# BrauV2_Power.net
KiCad netlist of a schematic drawn in Altium Designer
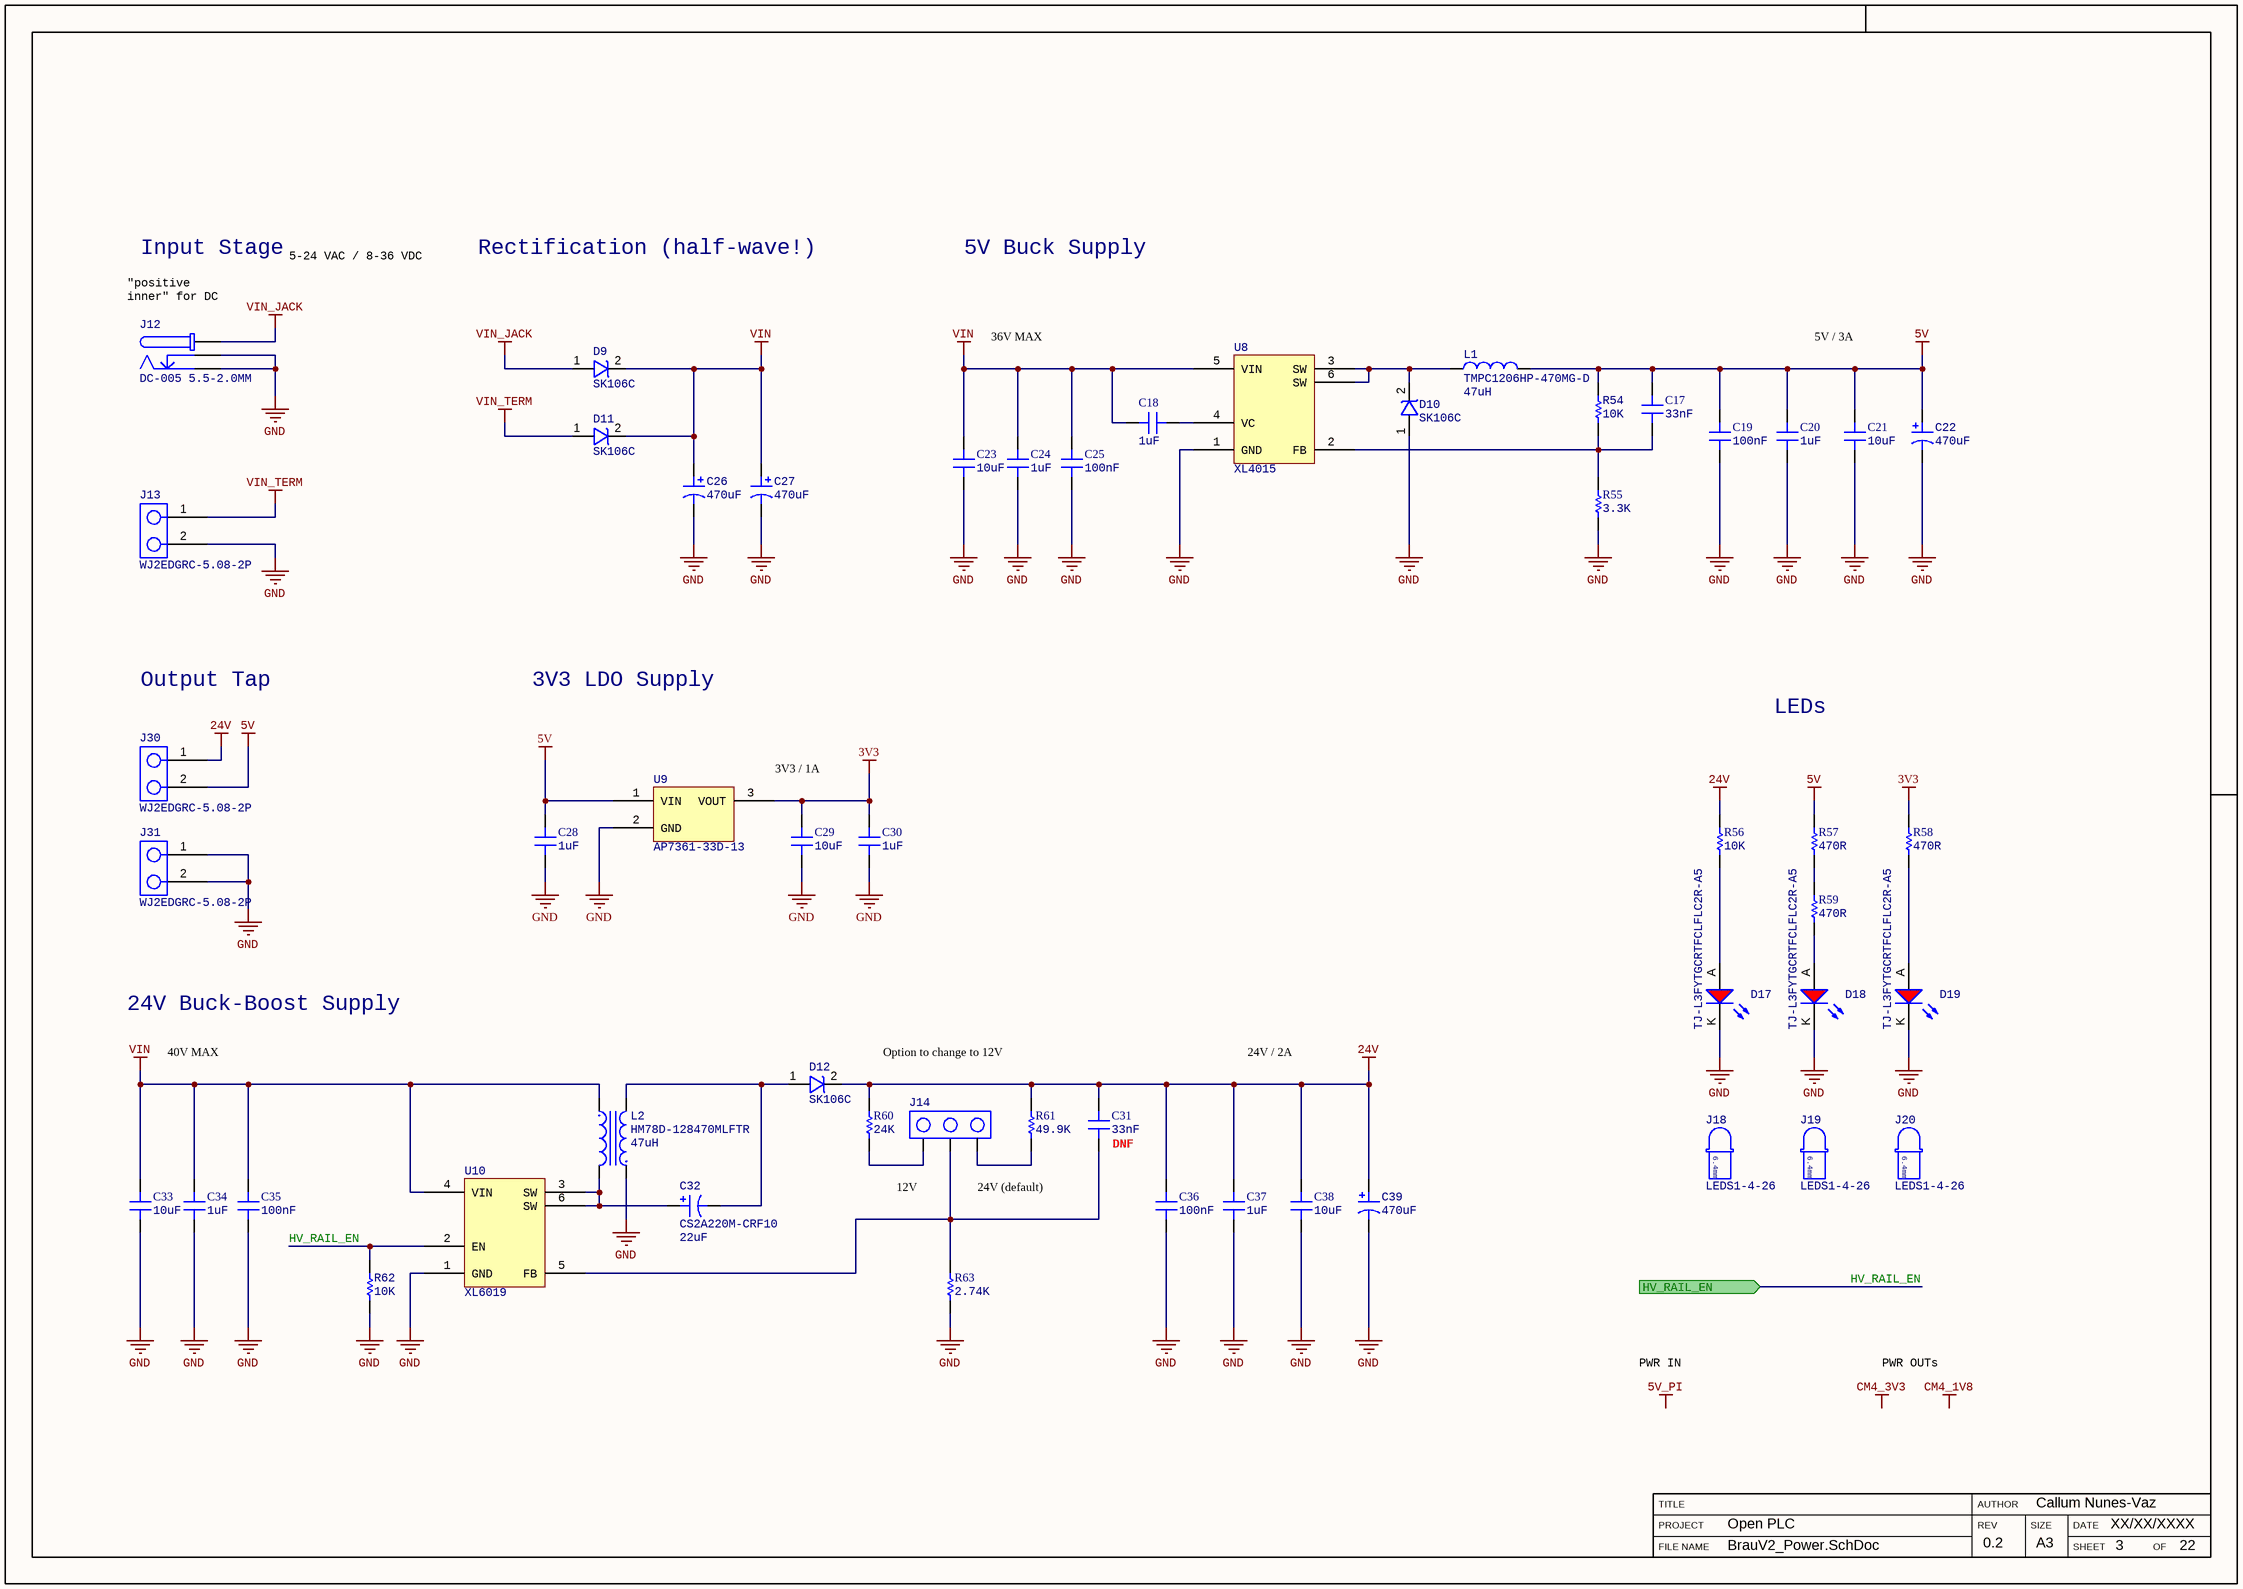
[diagram p0: BrauV2_Power.SchDoc]

(export (version "E")
  (design (tool "Eeschema 10.0.6"))
  (components
    (comp (ref "C17")
      (value "CC0402KRX7R9BB333")
      (footprint "SMD_CAP_0402(1005)_N")
      (description "33nF ±10% 50V X7R 0402 Multilayer Ceramic Capacitors MLCC - SMD/SMT RoHS")
      (fields (field (name "TOLERANCE") "10%") (field (name "CAPACITANCE") "33nF"))
      (libsource (lib "BrauV2_Capacitor") (part "33nF 0402 50V 10%"))
    )
    (comp (ref "C18")
      (value "CC0603KRX5R9BB105")
      (footprint "SMD_CAP_0603(0201)_N")
      (description "1uF ±10% 50V X5R 0603 Multilayer Ceramic Capacitors MLCC - SMD/SMT RoHS")
      (fields (field (name "TOLERANCE") "10%") (field (name "CAPACITANCE") "1uF"))
      (libsource (lib "BrauV2_Capacitor") (part "1uF 0603 50V 10%"))
    )
    (comp (ref "C19")
      (value "CC0402KRX5R9BB104")
      (footprint "SMD_CAP_0402(1005)_N")
      (description "100nF ±10% 50V X5R 0402 Multilayer Ceramic Capacitors MLCC - SMD/SMT RoHS")
      (fields (field (name "TOLERANCE") "10%") (field (name "CAPACITANCE") "100nF"))
      (libsource (lib "BrauV2_Capacitor") (part "100nF 0402 50V 10%"))
    )
    (comp (ref "C20")
      (value "CC0603KRX5R9BB105")
      (footprint "SMD_CAP_0603(0201)_N")
      (description "1uF ±10% 50V X5R 0603 Multilayer Ceramic Capacitors MLCC - SMD/SMT RoHS")
      (fields (field (name "TOLERANCE") "10%") (field (name "CAPACITANCE") "1uF"))
      (libsource (lib "BrauV2_Capacitor") (part "1uF 0603 50V 10%"))
    )
    (comp (ref "C21")
      (value "CC1206KKX5R9BB106")
      (footprint "SMD_CAP_1206(3216)_N")
      (description "10uF ±10% 50V X5R 1206 Multilayer Ceramic Capacitors MLCC - SMD/SMT RoHS")
      (fields (field (name "TOLERANCE") "10%") (field (name "CAPACITANCE") "10uF"))
      (libsource (lib "BrauV2_Capacitor") (part "10uF 1206 50V 10%"))
    )
    (comp (ref "C22")
      (value "CK1V471MCRG10")
      (footprint "CAP_SMD_10x10.5mm")
      (description "470uF ±20% 35V SMD,10x10.5mm Aluminum Electrolytic Capacitors - SMD RoHS")
      (fields (field (name "TOLERANCE") "20%") (field (name "CAPACITANCE") "470uF"))
      (libsource (lib "") (part "CK1V471MCRG10_1"))
    )
    (comp (ref "C23")
      (value "CC1206KKX5R9BB106")
      (footprint "SMD_CAP_1206(3216)_N")
      (description "10uF ±10% 50V X5R 1206 Multilayer Ceramic Capacitors MLCC - SMD/SMT RoHS")
      (fields (field (name "TOLERANCE") "10%") (field (name "CAPACITANCE") "10uF"))
      (libsource (lib "BrauV2_Capacitor") (part "10uF 1206 50V 10%"))
    )
    (comp (ref "C24")
      (value "CC0603KRX5R9BB105")
      (footprint "SMD_CAP_0603(0201)_N")
      (description "1uF ±10% 50V X5R 0603 Multilayer Ceramic Capacitors MLCC - SMD/SMT RoHS")
      (fields (field (name "TOLERANCE") "10%") (field (name "CAPACITANCE") "1uF"))
      (libsource (lib "BrauV2_Capacitor") (part "1uF 0603 50V 10%"))
    )
    (comp (ref "C25")
      (value "CC0402KRX5R9BB104")
      (footprint "SMD_CAP_0402(1005)_N")
      (description "100nF ±10% 50V X5R 0402 Multilayer Ceramic Capacitors MLCC - SMD/SMT RoHS")
      (fields (field (name "TOLERANCE") "10%") (field (name "CAPACITANCE") "100nF"))
      (libsource (lib "BrauV2_Capacitor") (part "100nF 0402 50V 10%"))
    )
    (comp (ref "C26")
      (value "CK1V471MCRG10")
      (footprint "CAP_SMD_10x10.5mm")
      (description "470uF ±20% 35V SMD,10x10.5mm Aluminum Electrolytic Capacitors - SMD RoHS")
      (fields (field (name "TOLERANCE") "20%") (field (name "CAPACITANCE") "470uF"))
      (libsource (lib "BrauV2_Capacitor") (part "CK1V471MCRG10"))
    )
    (comp (ref "C27")
      (value "CK1V471MCRG10")
      (footprint "CAP_SMD_10x10.5mm")
      (description "470uF ±20% 35V SMD,10x10.5mm Aluminum Electrolytic Capacitors - SMD RoHS")
      (fields (field (name "TOLERANCE") "20%") (field (name "CAPACITANCE") "470uF"))
      (libsource (lib "BrauV2_Capacitor") (part "CK1V471MCRG10"))
    )
    (comp (ref "C28")
      (value "CC0603KRX5R9BB105")
      (footprint "SMD_CAP_0603(0201)_N")
      (description "1uF ±10% 50V X5R 0603 Multilayer Ceramic Capacitors MLCC - SMD/SMT RoHS")
      (fields (field (name "TOLERANCE") "10%") (field (name "CAPACITANCE") "1uF"))
      (libsource (lib "BrauV2_Capacitor") (part "1uF 0603 50V 10%"))
    )
    (comp (ref "C29")
      (value "CC1206KKX5R9BB106")
      (footprint "SMD_CAP_1206(3216)_N")
      (description "10uF ±10% 50V X5R 1206 Multilayer Ceramic Capacitors MLCC - SMD/SMT RoHS")
      (fields (field (name "TOLERANCE") "10%") (field (name "CAPACITANCE") "10uF"))
      (libsource (lib "BrauV2_Capacitor") (part "10uF 1206 50V 10%"))
    )
    (comp (ref "C30")
      (value "CC0603KRX5R9BB105")
      (footprint "SMD_CAP_0603(0201)_N")
      (description "1uF ±10% 50V X5R 0603 Multilayer Ceramic Capacitors MLCC - SMD/SMT RoHS")
      (fields (field (name "TOLERANCE") "10%") (field (name "CAPACITANCE") "1uF"))
      (libsource (lib "BrauV2_Capacitor") (part "1uF 0603 50V 10%"))
    )
    (comp (ref "C31")
      (value "CC0402KRX7R9BB333")
      (footprint "SMD_CAP_0402(1005)_N")
      (description "33nF ±10% 50V X7R 0402 Multilayer Ceramic Capacitors MLCC - SMD/SMT RoHS")
      (fields (field (name "TOLERANCE") "10%") (field (name "CAPACITANCE") "33nF"))
      (libsource (lib "BrauV2_Capacitor") (part "33nF 0402 50V 10%"))
    )
    (comp (ref "C32")
      (value "CS2A220M-CRF10")
      (footprint "CAP_SMD_8x10.5mm")
      (description "22uF ±20% 100V SMD,8x10.5mm Aluminum Electrolytic Capacitors - SMD RoHS")
      (fields (field (name "TOLERANCE") "20%") (field (name "CAPACITANCE") "22uF"))
      (libsource (lib "BrauV2_Capacitor") (part "CS2A220M-CRF10"))
    )
    (comp (ref "C33")
      (value "CC1206KKX5R9BB106")
      (footprint "SMD_CAP_1206(3216)_N")
      (description "10uF ±10% 50V X5R 1206 Multilayer Ceramic Capacitors MLCC - SMD/SMT RoHS")
      (fields (field (name "TOLERANCE") "10%") (field (name "CAPACITANCE") "10uF"))
      (libsource (lib "BrauV2_Capacitor") (part "10uF 1206 50V 10%"))
    )
    (comp (ref "C34")
      (value "CC0603KRX5R9BB105")
      (footprint "SMD_CAP_0603(0201)_N")
      (description "1uF ±10% 50V X5R 0603 Multilayer Ceramic Capacitors MLCC - SMD/SMT RoHS")
      (fields (field (name "TOLERANCE") "10%") (field (name "CAPACITANCE") "1uF"))
      (libsource (lib "BrauV2_Capacitor") (part "1uF 0603 50V 10%"))
    )
    (comp (ref "C35")
      (value "CC0402KRX5R9BB104")
      (footprint "SMD_CAP_0402(1005)_N")
      (description "100nF ±10% 50V X5R 0402 Multilayer Ceramic Capacitors MLCC - SMD/SMT RoHS")
      (fields (field (name "TOLERANCE") "10%") (field (name "CAPACITANCE") "100nF"))
      (libsource (lib "BrauV2_Capacitor") (part "100nF 0402 50V 10%"))
    )
    (comp (ref "C36")
      (value "CC0402KRX5R9BB104")
      (footprint "SMD_CAP_0402(1005)_N")
      (description "100nF ±10% 50V X5R 0402 Multilayer Ceramic Capacitors MLCC - SMD/SMT RoHS")
      (fields (field (name "TOLERANCE") "10%") (field (name "CAPACITANCE") "100nF"))
      (libsource (lib "BrauV2_Capacitor") (part "100nF 0402 50V 10%"))
    )
    (comp (ref "C37")
      (value "CC0603KRX5R9BB105")
      (footprint "SMD_CAP_0603(0201)_N")
      (description "1uF ±10% 50V X5R 0603 Multilayer Ceramic Capacitors MLCC - SMD/SMT RoHS")
      (fields (field (name "TOLERANCE") "10%") (field (name "CAPACITANCE") "1uF"))
      (libsource (lib "BrauV2_Capacitor") (part "1uF 0603 50V 10%"))
    )
    (comp (ref "C38")
      (value "CC1206KKX5R9BB106")
      (footprint "SMD_CAP_1206(3216)_N")
      (description "10uF ±10% 50V X5R 1206 Multilayer Ceramic Capacitors MLCC - SMD/SMT RoHS")
      (fields (field (name "TOLERANCE") "10%") (field (name "CAPACITANCE") "10uF"))
      (libsource (lib "BrauV2_Capacitor") (part "10uF 1206 50V 10%"))
    )
    (comp (ref "C39")
      (value "CK1V471MCRG10")
      (footprint "CAP_SMD_10x10.5mm")
      (description "470uF ±20% 35V SMD,10x10.5mm Aluminum Electrolytic Capacitors - SMD RoHS")
      (fields (field (name "TOLERANCE") "20%") (field (name "CAPACITANCE") "470uF"))
      (libsource (lib "") (part "CK1V471MCRG10_1"))
    )
    (comp (ref "D9")
      (value "SK106C")
      (footprint "DO-214AB")
      (description "60V 10A 850mV @ 10A SMC(DO-214AB) Schottky Barrier Diodes (SBD) RoHS")
      (libsource (lib "BrauV2_Diode") (part "SK106C"))
    )
    (comp (ref "D10")
      (value "SK106C")
      (footprint "DO-214AB")
      (description "60V 10A 850mV @ 10A SMC(DO-214AB) Schottky Barrier Diodes (SBD) RoHS")
      (libsource (lib "BrauV2_Diode") (part "SK106C"))
    )
    (comp (ref "D11")
      (value "SK106C")
      (footprint "DO-214AB")
      (description "60V 10A 850mV @ 10A SMC(DO-214AB) Schottky Barrier Diodes (SBD) RoHS")
      (libsource (lib "BrauV2_Diode") (part "SK106C"))
    )
    (comp (ref "D12")
      (value "SK106C")
      (footprint "DO-214AB")
      (description "60V 10A 850mV @ 10A SMC(DO-214AB) Schottky Barrier Diodes (SBD) RoHS")
      (libsource (lib "BrauV2_Diode") (part "SK106C"))
    )
    (comp (ref "D17")
      (value "TJ-L3FYTGCRTFCLFLC2R-A5")
      (footprint "LED_3MM_SPACED_6.4MM_RED")
      (description "LED 3mm Red 620nm~630nm 1.8V~2.6V Through Hole Light Emitting Diodes (LED) RoHS C331031")
      (libsource (lib "BrauV2_Diode") (part "TJ-L3FYTGCRTFCLFLC2R-A5"))
    )
    (comp (ref "D18")
      (value "TJ-L3FYTGCRTFCLFLC2R-A5")
      (footprint "LED_3MM_SPACED_6.4MM_RED")
      (description "LED 3mm Red 620nm~630nm 1.8V~2.6V Through Hole Light Emitting Diodes (LED) RoHS C331031")
      (libsource (lib "BrauV2_Diode") (part "TJ-L3FYTGCRTFCLFLC2R-A5"))
    )
    (comp (ref "D19")
      (value "TJ-L3FYTGCRTFCLFLC2R-A5")
      (footprint "LED_3MM_SPACED_6.4MM_RED")
      (description "LED 3mm Red 620nm~630nm 1.8V~2.6V Through Hole Light Emitting Diodes (LED) RoHS C331031")
      (libsource (lib "BrauV2_Diode") (part "TJ-L3FYTGCRTFCLFLC2R-A5"))
    )
    (comp (ref "J12")
      (value "DC-005 5.5-2.0MM")
      (footprint "DC-005 5.5-2.0MM")
      (description "Through Hole AC/DC Power Plugs & Receptacles RoHS")
      (libsource (lib "BrauV2_Connector") (part "DC-005 5.5-2.0MM"))
    )
    (comp (ref "J13")
      (value "WJ2EDGRC-5.08-2P")
      (footprint "796638-2")
      (description "Covered（4Sided） 2 1 0.200\"（5.08mm） 2 P=5.08mm Pluggable System Terminal Block RoHS")
      (libsource (lib "BrauV2_Connector") (part "WJ2EDGRC-5.08-2P"))
    )
    (comp (ref "J14")
      (value "12251103CNG0S115001")
      (footprint "Header_3POS")
      (description "Pin Header 3 1 right-angle，180degrees 2.54mm Through Hole,P=2.54mm Pin Header & Female Header RoHS")
      (libsource (lib "BrauV2_Connector") (part "3-way Jumper"))
    )
    (comp (ref "J18")
      (value "LEDS1-4-26")
      (footprint "3MM_LED_SPACER_6.4MM")
      (description "3mm LED spacer 6.4mm height")
      (libsource (lib "BrauV2_Misc") (part "LEDS1-4-26"))
    )
    (comp (ref "J19")
      (value "LEDS1-4-26")
      (footprint "3MM_LED_SPACER_6.4MM")
      (description "3mm LED spacer 6.4mm height")
      (libsource (lib "BrauV2_Misc") (part "LEDS1-4-26"))
    )
    (comp (ref "J20")
      (value "LEDS1-4-26")
      (footprint "3MM_LED_SPACER_6.4MM")
      (description "3mm LED spacer 6.4mm height")
      (libsource (lib "BrauV2_Misc") (part "LEDS1-4-26"))
    )
    (comp (ref "J30")
      (value "WJ2EDGRC-5.08-2P")
      (footprint "796638-2")
      (description "Covered（4Sided） 2 1 0.200\"（5.08mm） 2 P=5.08mm Pluggable System Terminal Block RoHS")
      (libsource (lib "BrauV2_Connector") (part "WJ2EDGRC-5.08-2P"))
    )
    (comp (ref "J31")
      (value "WJ2EDGRC-5.08-2P")
      (footprint "796638-2")
      (description "Covered（4Sided） 2 1 0.200\"（5.08mm） 2 P=5.08mm Pluggable System Terminal Block RoHS")
      (libsource (lib "BrauV2_Connector") (part "WJ2EDGRC-5.08-2P"))
    )
    (comp (ref "L1")
      (value "TMPC1206HP-470MG-D")
      (footprint "TMPC1206HP-470MG-D")
      (description "47uH ±20% 5.5A 80mΩ SMD,13.5x12.5x5.7mm Power Inductors RoHS")
      (fields (field (name "INDUCTANCE") "47uH"))
      (libsource (lib "BrauV2_Inductor") (part "TMPC1206HP-470MG-D"))
    )
    (comp (ref "L2")
      (value "HM78D-128470MLFTR")
      (footprint "HM78D-128470MLFTR")
      (description "Coupled Inductors 47uH 20%")
      (fields (field (name "PARALLEL INDUCTANCE") "47uH"))
      (libsource (lib "BrauV2_Inductor") (part "HM78D-128470MLFTR"))
    )
    (comp (ref "R54")
      (value "RC0402FR-0710KL")
      (footprint "SMD_RES_0402(1005)_N")
      (description "10kΩ ±1% 1/16W ±100ppm/℃ 0402 Chip Resistor - Surface Mount RoHS")
      (fields (field (name "TOLERANCE") "1%") (field (name "RESISTANCE") "10K"))
      (libsource (lib "BrauV2_Resistor") (part "10K 0402 1% 1/16W"))
    )
    (comp (ref "R55")
      (value "RC0402FR-073K3L")
      (footprint "SMD_RES_0402(1005)_N")
      (description "3.3kΩ ±1% 1/16W ±100ppm/℃ 0402 Chip Resistor - Surface Mount RoHS")
      (fields (field (name "TOLERANCE") "1%") (field (name "RESISTANCE") "3.3K"))
      (libsource (lib "BrauV2_Resistor") (part "3K3 0402 1% 1/16W"))
    )
    (comp (ref "R56")
      (value "RC0402FR-0710KL")
      (footprint "SMD_RES_0402(1005)_N")
      (description "10kΩ ±1% 1/16W ±100ppm/℃ 0402 Chip Resistor - Surface Mount RoHS")
      (fields (field (name "TOLERANCE") "1%") (field (name "RESISTANCE") "10K"))
      (libsource (lib "BrauV2_Resistor") (part "10K 0402 1% 1/16W"))
    )
    (comp (ref "R57")
      (value "RC0402FR-07470RL")
      (footprint "SMD_RES_0402(1005)_N")
      (description "470Ω ±1% 1/16W ±100ppm/℃ 0402 Chip Resistor - Surface Mount RoHS")
      (fields (field (name "TOLERANCE") "1%") (field (name "RESISTANCE") "470R"))
      (libsource (lib "BrauV2_Resistor") (part "470R 0402 1% 1W"))
    )
    (comp (ref "R58")
      (value "RC0402FR-07470RL")
      (footprint "SMD_RES_0402(1005)_N")
      (description "470Ω ±1% 1/16W ±100ppm/℃ 0402 Chip Resistor - Surface Mount RoHS")
      (fields (field (name "TOLERANCE") "1%") (field (name "RESISTANCE") "470R"))
      (libsource (lib "BrauV2_Resistor") (part "470R 0402 1% 1W"))
    )
    (comp (ref "R59")
      (value "RC0402FR-07470RL")
      (footprint "SMD_RES_0402(1005)_N")
      (description "470Ω ±1% 1/16W ±100ppm/℃ 0402 Chip Resistor - Surface Mount RoHS")
      (fields (field (name "TOLERANCE") "1%") (field (name "RESISTANCE") "470R"))
      (libsource (lib "BrauV2_Resistor") (part "470R 0402 1% 1W"))
    )
    (comp (ref "R60")
      (value "RC0402FR-0724KL")
      (footprint "SMD_RES_0402(1005)_N")
      (description "24kΩ ±1% 1/16W ±100ppm/℃ 0402 Chip Resistor - Surface Mount RoHS")
      (fields (field (name "TOLERANCE") "1%") (field (name "RESISTANCE") "24K"))
      (libsource (lib "BrauV2_Resistor") (part "24K 0402 1% 1/16W"))
    )
    (comp (ref "R61")
      (value "RC0402FR-0749K9L")
      (footprint "SMD_RES_0402(1005)_N")
      (description "49.9kΩ ±1% 1/16W ±100ppm/℃ 0402 Chip Resistor - Surface Mount RoHS")
      (fields (field (name "TOLERANCE") "1%") (field (name "RESISTANCE") "49.9K"))
      (libsource (lib "BrauV2_Resistor") (part "49K9 0402 1% 1/16W"))
    )
    (comp (ref "R62")
      (value "RC0402FR-0710KL")
      (footprint "SMD_RES_0402(1005)_N")
      (description "10kΩ ±1% 1/16W ±100ppm/℃ 0402 Chip Resistor - Surface Mount RoHS")
      (fields (field (name "TOLERANCE") "1%") (field (name "RESISTANCE") "10K"))
      (libsource (lib "BrauV2_Resistor") (part "10K 0402 1% 1/16W"))
    )
    (comp (ref "R63")
      (value "RC0402FR-072K74L")
      (footprint "SMD_RES_0402(1005)_N")
      (description "2.74kΩ ±1% 1/16W ±100ppm/℃ 0402 Chip Resistor - Surface Mount RoHS")
      (fields (field (name "TOLERANCE") "1%") (field (name "RESISTANCE") "2.74K"))
      (libsource (lib "BrauV2_Resistor") (part "2K74 0402 1% 1/16W"))
    )
    (comp (ref "U8")
      (value "XL4015")
      (footprint "TO-263-5")
      (description "XLSEMI 5A 180KHz 36V Buck DC to DC Converter")
      (libsource (lib "BrauV2_IC") (part "XL4015"))
    )
    (comp (ref "U9")
      (value "AP7361-33D-13")
      (footprint "TO-252")
      (description "Fixed 6V 3.3V 700mV @ 1A TO-252 Dropout Regulators(LDO) RoHS")
      (libsource (lib "BrauV2_IC") (part "AP7361-33D-13"))
    )
    (comp (ref "U10")
      (value "XL6019")
      (footprint "TO-263-5")
      (description "XLSEMI 180KHz 60V 5A Switching Current Boost / Buck-Boost / Inverting DC/DC Converter")
      (libsource (lib "BrauV2_IC") (part "XL6019"))
    )
  )
  (nets
    (net (code "1") (name "/HV_RAIL_EN") (class "Default")
      (node (ref "R62") (pin "2") (pinfunction "2_2") (pintype "passive"))
      (node (ref "U10") (pin "2") (pinfunction "EN_2") (pintype "passive"))
    )
    (net (code "2") (name "3V3") (class "Default")
      (node (ref "C29") (pin "2") (pinfunction "2_2") (pintype "passive"))
      (node (ref "C30") (pin "2") (pinfunction "2_2") (pintype "passive"))
      (node (ref "R58") (pin "2") (pinfunction "2_2") (pintype "passive"))
      (node (ref "U9") (pin "3") (pinfunction "VOUT_3") (pintype "passive"))
    )
    (net (code "3") (name "5V") (class "Default")
      (node (ref "C17") (pin "2") (pinfunction "2_2") (pintype "passive"))
      (node (ref "C19") (pin "2") (pinfunction "2_2") (pintype "passive"))
      (node (ref "C20") (pin "2") (pinfunction "2_2") (pintype "passive"))
      (node (ref "C21") (pin "2") (pinfunction "2_2") (pintype "passive"))
      (node (ref "C22") (pin "1") (pinfunction "1_1") (pintype "passive"))
      (node (ref "C28") (pin "2") (pinfunction "2_2") (pintype "passive"))
      (node (ref "J30") (pin "2") (pinfunction "2_2") (pintype "passive"))
      (node (ref "L1") (pin "2") (pinfunction "2_2") (pintype "passive"))
      (node (ref "R54") (pin "2") (pinfunction "2_2") (pintype "passive"))
      (node (ref "R57") (pin "2") (pinfunction "2_2") (pintype "passive"))
      (node (ref "U9") (pin "1") (pinfunction "VIN_1") (pintype "passive"))
    )
    (net (code "5") (name "24V") (class "Default")
      (node (ref "C31") (pin "2") (pinfunction "2_2") (pintype "passive"))
      (node (ref "C36") (pin "2") (pinfunction "2_2") (pintype "passive"))
      (node (ref "C37") (pin "2") (pinfunction "2_2") (pintype "passive"))
      (node (ref "C38") (pin "2") (pinfunction "2_2") (pintype "passive"))
      (node (ref "C39") (pin "1") (pinfunction "1_1") (pintype "passive"))
      (node (ref "D12") (pin "2") (pinfunction "CATHODE_2") (pintype "passive"))
      (node (ref "J30") (pin "1") (pinfunction "1_1") (pintype "passive"))
      (node (ref "R56") (pin "2") (pinfunction "2_2") (pintype "passive"))
      (node (ref "R60") (pin "2") (pinfunction "2_2") (pintype "passive"))
      (node (ref "R61") (pin "2") (pinfunction "2_2") (pintype "passive"))
    )
    (net (code "8") (name "GND") (class "Default")
      (node (ref "C19") (pin "1") (pinfunction "1_1") (pintype "passive"))
      (node (ref "C20") (pin "1") (pinfunction "1_1") (pintype "passive"))
      (node (ref "C21") (pin "1") (pinfunction "1_1") (pintype "passive"))
      (node (ref "C22") (pin "2") (pinfunction "2_2") (pintype "passive"))
      (node (ref "C23") (pin "1") (pinfunction "1_1") (pintype "passive"))
      (node (ref "C24") (pin "1") (pinfunction "1_1") (pintype "passive"))
      (node (ref "C25") (pin "1") (pinfunction "1_1") (pintype "passive"))
      (node (ref "C26") (pin "2") (pinfunction "2_2") (pintype "passive"))
      (node (ref "C27") (pin "2") (pinfunction "2_2") (pintype "passive"))
      (node (ref "C28") (pin "1") (pinfunction "1_1") (pintype "passive"))
      (node (ref "C29") (pin "1") (pinfunction "1_1") (pintype "passive"))
      (node (ref "C30") (pin "1") (pinfunction "1_1") (pintype "passive"))
      (node (ref "C33") (pin "1") (pinfunction "1_1") (pintype "passive"))
      (node (ref "C34") (pin "1") (pinfunction "1_1") (pintype "passive"))
      (node (ref "C35") (pin "1") (pinfunction "1_1") (pintype "passive"))
      (node (ref "C36") (pin "1") (pinfunction "1_1") (pintype "passive"))
      (node (ref "C37") (pin "1") (pinfunction "1_1") (pintype "passive"))
      (node (ref "C38") (pin "1") (pinfunction "1_1") (pintype "passive"))
      (node (ref "C39") (pin "2") (pinfunction "2_2") (pintype "passive"))
      (node (ref "D10") (pin "1") (pinfunction "ANODE_1") (pintype "passive"))
      (node (ref "D17") (pin "K") (pinfunction "K_K") (pintype "passive"))
      (node (ref "D18") (pin "K") (pinfunction "K_K") (pintype "passive"))
      (node (ref "D19") (pin "K") (pinfunction "K_K") (pintype "passive"))
      (node (ref "J12") (pin "2") (pinfunction "2_2") (pintype "passive"))
      (node (ref "J12") (pin "3") (pinfunction "3_3") (pintype "passive"))
      (node (ref "J13") (pin "2") (pinfunction "2_2") (pintype "passive"))
      (node (ref "J31") (pin "1") (pinfunction "1_1") (pintype "passive"))
      (node (ref "J31") (pin "2") (pinfunction "2_2") (pintype "passive"))
      (node (ref "L2") (pin "1") (pinfunction "1_1") (pintype "passive"))
      (node (ref "R55") (pin "1") (pinfunction "1_1") (pintype "passive"))
      (node (ref "R62") (pin "1") (pinfunction "1_1") (pintype "passive"))
      (node (ref "R63") (pin "1") (pinfunction "1_1") (pintype "passive"))
      (node (ref "U10") (pin "1") (pinfunction "GND_1") (pintype "passive"))
      (node (ref "U8") (pin "1") (pinfunction "GND_1") (pintype "passive"))
      (node (ref "U9") (pin "2") (pinfunction "GND_2") (pintype "passive"))
    )
    (net (code "9") (name "Net-(C32-Pad1)") (class "Default")
      (node (ref "C32") (pin "1") (pinfunction "1_1") (pintype "passive"))
      (node (ref "L2") (pin "4") (pinfunction "4_4") (pintype "passive"))
      (node (ref "U10") (pin "3") (pinfunction "SW_3") (pintype "passive"))
      (node (ref "U10") (pin "6") (pinfunction "SW_6") (pintype "passive"))
    )
    (net (code "10") (name "Net-(D10-CATHODE)") (class "Default")
      (node (ref "D10") (pin "2") (pinfunction "CATHODE_2") (pintype "passive"))
      (node (ref "L1") (pin "1") (pinfunction "1_1") (pintype "passive"))
      (node (ref "U8") (pin "3") (pinfunction "SW_3") (pintype "passive"))
      (node (ref "U8") (pin "6") (pinfunction "SW_6") (pintype "passive"))
    )
    (net (code "11") (name "Net-(D12-ANODE)") (class "Default")
      (node (ref "C32") (pin "2") (pinfunction "2_2") (pintype "passive"))
      (node (ref "D12") (pin "1") (pinfunction "ANODE_1") (pintype "passive"))
      (node (ref "L2") (pin "3") (pinfunction "3_3") (pintype "passive"))
    )
    (net (code "12") (name "Net-(D17-PadA)") (class "Default")
      (node (ref "D17") (pin "A") (pinfunction "A_A") (pintype "passive"))
      (node (ref "R56") (pin "1") (pinfunction "1_1") (pintype "passive"))
    )
    (net (code "13") (name "Net-(D18-PadA)") (class "Default")
      (node (ref "D18") (pin "A") (pinfunction "A_A") (pintype "passive"))
      (node (ref "R59") (pin "1") (pinfunction "1_1") (pintype "passive"))
    )
    (net (code "14") (name "Net-(D19-PadA)") (class "Default")
      (node (ref "D19") (pin "A") (pinfunction "A_A") (pintype "passive"))
      (node (ref "R58") (pin "1") (pinfunction "1_1") (pintype "passive"))
    )
    (net (code "15") (name "Net-(J14-Pad1)") (class "Default")
      (node (ref "J14") (pin "1") (pinfunction "1_1") (pintype "passive"))
      (node (ref "R60") (pin "1") (pinfunction "1_1") (pintype "passive"))
    )
    (net (code "16") (name "Net-(J14-Pad3)") (class "Default")
      (node (ref "J14") (pin "3") (pinfunction "3_3") (pintype "passive"))
      (node (ref "R61") (pin "1") (pinfunction "1_1") (pintype "passive"))
    )
    (net (code "17") (name "Net-(R57-Pad1)") (class "Default")
      (node (ref "R57") (pin "1") (pinfunction "1_1") (pintype "passive"))
      (node (ref "R59") (pin "2") (pinfunction "2_2") (pintype "passive"))
    )
    (net (code "18") (name "Net-(U8-FB)") (class "Default")
      (node (ref "C17") (pin "1") (pinfunction "1_1") (pintype "passive"))
      (node (ref "R54") (pin "1") (pinfunction "1_1") (pintype "passive"))
      (node (ref "R55") (pin "2") (pinfunction "2_2") (pintype "passive"))
      (node (ref "U8") (pin "2") (pinfunction "FB_2") (pintype "passive"))
    )
    (net (code "19") (name "Net-(U8-VC)") (class "Default")
      (node (ref "C18") (pin "1") (pinfunction "1_1") (pintype "passive"))
      (node (ref "U8") (pin "4") (pinfunction "VC_4") (pintype "passive"))
    )
    (net (code "20") (name "Net-(U10-FB)") (class "Default")
      (node (ref "C31") (pin "1") (pinfunction "1_1") (pintype "passive"))
      (node (ref "J14") (pin "2") (pinfunction "2_2") (pintype "passive"))
      (node (ref "R63") (pin "2") (pinfunction "2_2") (pintype "passive"))
      (node (ref "U10") (pin "5") (pinfunction "FB_5") (pintype "passive"))
    )
    (net (code "21") (name "VIN") (class "Default")
      (node (ref "C18") (pin "2") (pinfunction "2_2") (pintype "passive"))
      (node (ref "C23") (pin "2") (pinfunction "2_2") (pintype "passive"))
      (node (ref "C24") (pin "2") (pinfunction "2_2") (pintype "passive"))
      (node (ref "C25") (pin "2") (pinfunction "2_2") (pintype "passive"))
      (node (ref "C26") (pin "1") (pinfunction "1_1") (pintype "passive"))
      (node (ref "C27") (pin "1") (pinfunction "1_1") (pintype "passive"))
      (node (ref "C33") (pin "2") (pinfunction "2_2") (pintype "passive"))
      (node (ref "C34") (pin "2") (pinfunction "2_2") (pintype "passive"))
      (node (ref "C35") (pin "2") (pinfunction "2_2") (pintype "passive"))
      (node (ref "D11") (pin "2") (pinfunction "CATHODE_2") (pintype "passive"))
      (node (ref "D9") (pin "2") (pinfunction "CATHODE_2") (pintype "passive"))
      (node (ref "L2") (pin "2") (pinfunction "2_2") (pintype "passive"))
      (node (ref "U10") (pin "4") (pinfunction "VIN_4") (pintype "passive"))
      (node (ref "U8") (pin "5") (pinfunction "VIN_5") (pintype "passive"))
    )
    (net (code "22") (name "VIN_JACK") (class "Default")
      (node (ref "D9") (pin "1") (pinfunction "ANODE_1") (pintype "passive"))
      (node (ref "J12") (pin "4") (pinfunction "4_4") (pintype "passive"))
    )
    (net (code "23") (name "VIN_TERM") (class "Default")
      (node (ref "D11") (pin "1") (pinfunction "ANODE_1") (pintype "passive"))
      (node (ref "J13") (pin "1") (pinfunction "1_1") (pintype "passive"))
    )
  )
)
